# CH32F_V208W-R0.net
KiCad netlist of a schematic drawn in Altium Designer
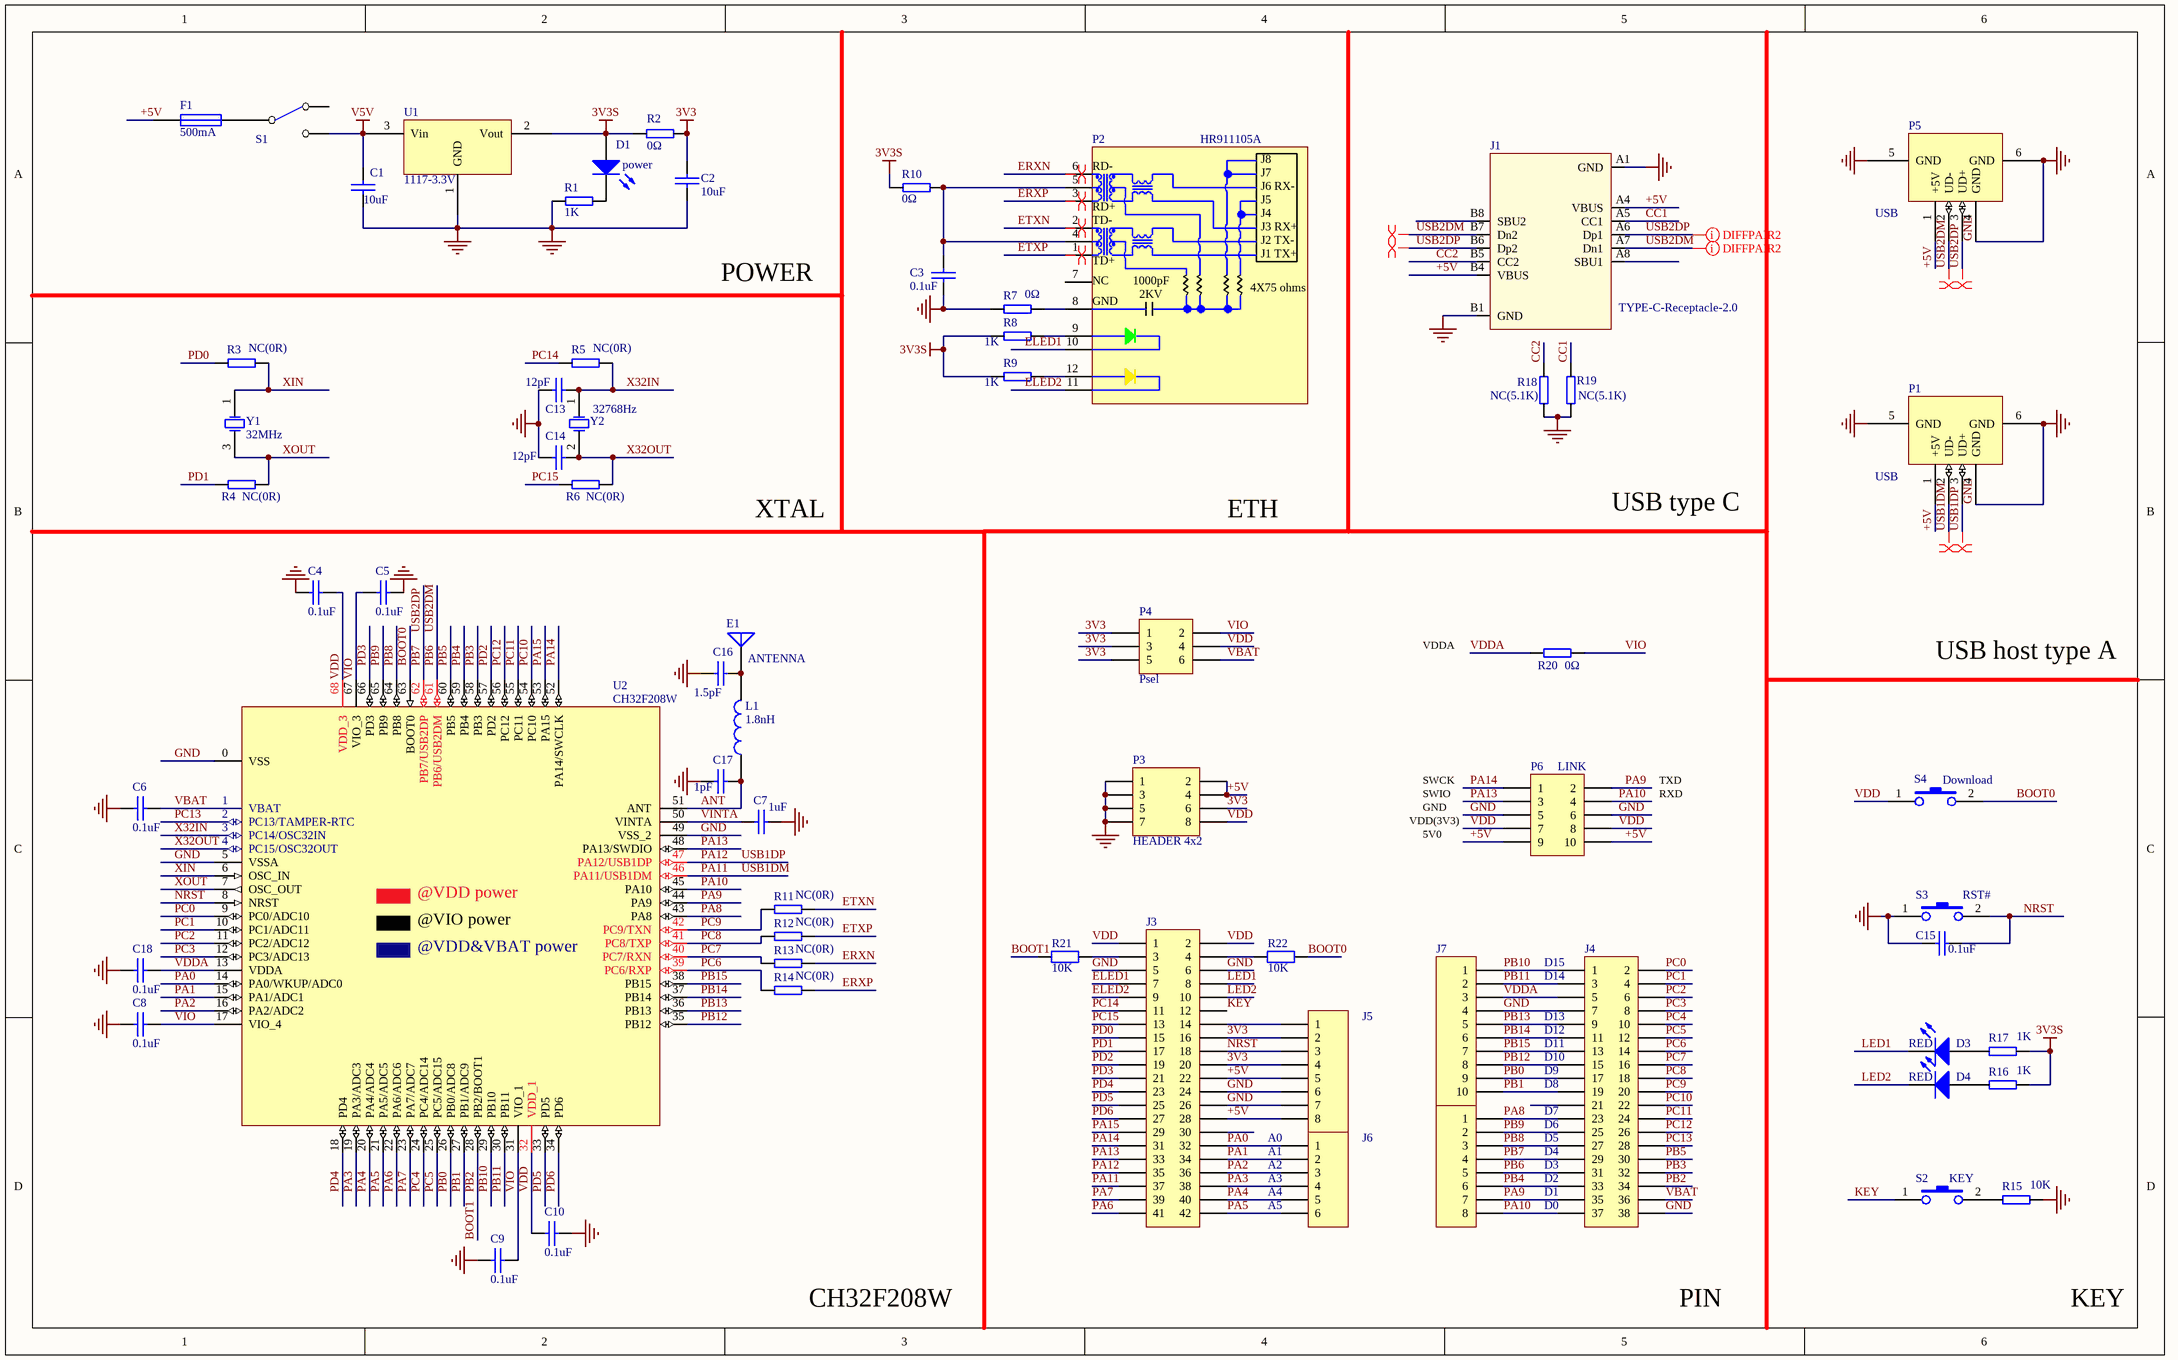
[diagram p0: CH32F&V208W-R0.SchDoc]

(export (version "E")
  (design (tool "Eeschema 10.0.6"))
  (components
    (comp (ref "C1")
      (value "10uF")
      (footprint "3216_C")
      (description "Capacitor")
      (libsource (lib "*") (part "CAP"))
    )
    (comp (ref "C2")
      (value "10uF")
      (footprint "0603_C")
      (description "Capacitor")
      (libsource (lib "*") (part "CAP"))
    )
    (comp (ref "C3")
      (value "0.1uF")
      (footprint "0603_C")
      (description "Capacitor")
      (libsource (lib "*") (part "CAP"))
    )
    (comp (ref "C4")
      (value "0.1uF")
      (footprint "0603_C")
      (description "Capacitor")
      (libsource (lib "") (part "CAP_1"))
    )
    (comp (ref "C5")
      (value "0.1uF")
      (footprint "0603_C")
      (description "Capacitor")
      (libsource (lib "") (part "CAP_1"))
    )
    (comp (ref "C6")
      (value "0.1uF")
      (footprint "0603_C")
      (description "Capacitor")
      (libsource (lib "") (part "CAP_1"))
    )
    (comp (ref "C7")
      (value "1uF")
      (footprint "0603_C")
      (description "Capacitor")
      (libsource (lib "") (part "CAP_1"))
    )
    (comp (ref "C8")
      (value "0.1uF")
      (footprint "0603_C")
      (description "Capacitor")
      (libsource (lib "") (part "CAP_1"))
    )
    (comp (ref "C9")
      (value "0.1uF")
      (footprint "0603_C")
      (description "Capacitor")
      (libsource (lib "") (part "CAP_1"))
    )
    (comp (ref "C10")
      (value "0.1uF")
      (footprint "0603_C")
      (description "Capacitor")
      (libsource (lib "") (part "CAP_1"))
    )
    (comp (ref "C13")
      (value "12pF")
      (footprint "0603_C")
      (description "Capacitor")
      (libsource (lib "*") (part "CAP"))
    )
    (comp (ref "C14")
      (value "12pF")
      (footprint "0603_C")
      (description "Capacitor")
      (libsource (lib "*") (part "CAP"))
    )
    (comp (ref "C15")
      (value "0.1uF")
      (footprint "0603_C")
      (description "Capacitor")
      (libsource (lib "") (part "CAP_1"))
    )
    (comp (ref "C16")
      (value "1.5pF")
      (footprint "0603_C")
      (description "Capacitor")
      (libsource (lib "") (part "CAP_1"))
    )
    (comp (ref "C17")
      (value "1pF")
      (footprint "0603_C")
      (description "Capacitor")
      (libsource (lib "") (part "CAP_1"))
    )
    (comp (ref "C18")
      (value "0.1uF")
      (footprint "0603_C")
      (description "Capacitor")
      (libsource (lib "") (part "CAP_1"))
    )
    (comp (ref "D1")
      (value "power")
      (footprint "0603+")
      (description "Typical INFRARED GaAs LED")
      (fields (field (name "PUBLISHER") "Altium Limited"))
      (libsource (lib "*") (part "LED0"))
    )
    (comp (ref "D3")
      (value "RED")
      (footprint "0603+")
      (description "Typical INFRARED GaAs LED")
      (fields (field (name "PUBLISHER") "Altium Limited"))
      (libsource (lib "*") (part "LED0"))
    )
    (comp (ref "D4")
      (value "RED")
      (footprint "0603+")
      (description "Typical INFRARED GaAs LED")
      (fields (field (name "PUBLISHER") "Altium Limited"))
      (libsource (lib "*") (part "LED0"))
    )
    (comp (ref "E1")
      (value "ANTENNA")
      (footprint "MYPCB:ANT-F-1-2.4G-1.6")
      (description "Generic Antenna")
      (libsource (lib "*") (part "ANTENNA"))
    )
    (comp (ref "F1")
      (value "500mA")
      (footprint "0603")
      (description "Fuse")
      (libsource (lib "wch_sch_others") (part "FUSE1"))
    )
    (comp (ref "J1")
      (value "TYPE-C-Receptacle-2.0")
      (footprint "TYPE-C-Receptacle-2.0")
      (description "Type-C USB2.0 母座")
      (libsource (lib "Miscellaneous SCH Lib") (part "TYPE-C-Receptacle-2.0"))
    )
    (comp (ref "J3")
      (value "Header 21X2")
      (footprint "IDC42-2.54mm")
      (description "Header, 21-Pin, Dual row")
      (fields (field (name "PUBLISHER") "Altium Limited"))
      (libsource (lib "PCB_Project") (part "Header 21X2"))
    )
    (comp (ref "J4")
      (value "Header 19X2")
      (footprint "IDC38-2.54mm")
      (description "Header, 19-Pin, Dual row")
      (fields (field (name "PUBLISHER") "Altium Limited"))
      (libsource (lib "Miscellaneous Connectors") (part "Header 19X2"))
    )
    (comp (ref "J5")
      (value "Header 8")
      (footprint "SIP8-2.54mm")
      (description "Header, 8-Pin")
      (fields (field (name "PUBLISHER") "Altium Limited"))
      (libsource (lib "") (part "Header 8_1"))
    )
    (comp (ref "J6")
      (value "Header 6")
      (footprint "SIP6-2.54MM")
      (description "Header, 6-Pin")
      (fields (field (name "PUBLISHER") "Altium Limited"))
      (libsource (lib "Miscellaneous Connectors") (part "Header 6"))
    )
    (comp (ref "J7")
      (value "Header 10")
      (footprint "SIP10-2.54mm")
      (description "Header, 10-Pin")
      (fields (field (name "PUBLISHER") "Altium Limited"))
      (libsource (lib "Miscellaneous Connectors") (part "Header 10"))
    )
    (comp (ref "J8")
      (value "Header 8")
      (footprint "SIP8-2.54mm")
      (description "Header, 8-Pin")
      (fields (field (name "PUBLISHER") "Altium Limited"))
      (libsource (lib "Miscellaneous Connectors") (part "Header 8"))
    )
    (comp (ref "L1") (value "1.8nH") (footprint "0603") (libsource (lib "*") (part "INDUCTOR")))
    (comp (ref "P1")
      (value "USB")
      (footprint "USBAF")
      (description "USB Port")
      (libsource (lib "*") (part "USB"))
    )
    (comp (ref "P2") (value "HR911105A") (footprint "HR911105A") (libsource (lib "*") (part "HR911105A")))
    (comp (ref "P3")
      (value "HEADER 4x2")
      (footprint "MYPCB:IDC8-2.54mm")
      (description "Header, 4-Pin, Dual row")
      (libsource (lib "wch_sch_others") (part "HEADER 4x2"))
    )
    (comp (ref "P4")
      (value "Psel")
      (footprint "IDC6-2.54mm")
      (description "Header, 3-Pin, Dual row, Right Angle")
      (fields (field (name "PUBLISHER") "Altium Limited"))
      (libsource (lib "Miscellaneous Connectors") (part "Header 3X2H"))
    )
    (comp (ref "P5")
      (value "USB")
      (footprint "USBAF")
      (description "USB Port")
      (libsource (lib "*") (part "USB"))
    )
    (comp (ref "P6")
      (value "LINK")
      (footprint "IDC10-2.54mm")
      (description "Header, 5-Pin, Dual row, Right Angle")
      (fields (field (name "PUBLISHER") "Altium Limited"))
      (libsource (lib "Miscellaneous Connectors") (part "Header 5X2H"))
    )
    (comp (ref "R1") (value "1K") (footprint "0603") (libsource (lib "wch_sch_others") (part "RES")))
    (comp (ref "R2") (value "0Ω") (footprint "0603") (libsource (lib "wch_sch_others") (part "RES")))
    (comp (ref "R3") (value "NC(0R)") (footprint "0603") (libsource (lib "wch_sch_others") (part "RES")))
    (comp (ref "R4") (value "NC(0R)") (footprint "0603") (libsource (lib "wch_sch_others") (part "RES")))
    (comp (ref "R5") (value "NC(0R)") (footprint "0603") (libsource (lib "wch_sch_others") (part "RES")))
    (comp (ref "R6") (value "NC(0R)") (footprint "0603") (libsource (lib "wch_sch_others") (part "RES")))
    (comp (ref "R7") (value "0Ω") (footprint "0603") (libsource (lib "wch_sch_others") (part "RES")))
    (comp (ref "R8") (value "1K") (footprint "0603") (libsource (lib "wch_sch_others") (part "RES")))
    (comp (ref "R9") (value "1K") (footprint "0603") (libsource (lib "wch_sch_others") (part "RES")))
    (comp (ref "R10") (value "0Ω") (footprint "0603") (libsource (lib "wch_sch_others") (part "RES")))
    (comp (ref "R11") (value "NC(0R)") (footprint "0603") (libsource (lib "wch_sch_others") (part "RES")))
    (comp (ref "R12") (value "NC(0R)") (footprint "0603") (libsource (lib "wch_sch_others") (part "RES")))
    (comp (ref "R13") (value "NC(0R)") (footprint "0603") (libsource (lib "wch_sch_others") (part "RES")))
    (comp (ref "R14") (value "NC(0R)") (footprint "0603") (libsource (lib "wch_sch_others") (part "RES")))
    (comp (ref "R15") (value "10K") (footprint "0603") (libsource (lib "wch_sch_others") (part "RES")))
    (comp (ref "R16") (value "1K") (footprint "0603") (libsource (lib "wch_sch_others") (part "RES")))
    (comp (ref "R17") (value "1K") (footprint "0603") (libsource (lib "wch_sch_others") (part "RES")))
    (comp (ref "R18") (value "NC(5.1K)") (footprint "0603") (libsource (lib "wch_sch_others") (part "RES")))
    (comp (ref "R19") (value "NC(5.1K)") (footprint "0603") (libsource (lib "wch_sch_others") (part "RES")))
    (comp (ref "R20") (value "0Ω") (footprint "0603") (libsource (lib "*") (part "R")))
    (comp (ref "R21")
      (value "10K")
      (footprint "0603")
      (description "Resistor")
      (libsource (lib "Miscellaneous Devices") (part "Res2"))
    )
    (comp (ref "R22")
      (value "10K")
      (footprint "0603")
      (description "Resistor")
      (libsource (lib "Miscellaneous Devices") (part "Res2"))
    )
    (comp (ref "S1") (value "SW SPDT") (footprint "KEY_B") (libsource (lib "*") (part "SW SPDT")))
    (comp (ref "S2")
      (value "KEY")
      (footprint "SMD_6.1x3.65x2.5mm-KEY")
      (libsource (lib "wch_sch_others") (part "KEY1"))
    )
    (comp (ref "S3")
      (value "RST#")
      (footprint "SMD_6.1x3.65x2.5mm-KEY")
      (libsource (lib "wch_sch_others") (part "KEY1"))
    )
    (comp (ref "S4")
      (value "Download")
      (footprint "SMD_6.1x3.65x2.5mm-KEY")
      (libsource (lib "wch_sch_others") (part "KEY1"))
    )
    (comp (ref "U1")
      (value "1117-3.3V")
      (footprint "SOT-223")
      (libsource (lib "wch_sch_others") (part "1117-3.3V"))
    )
    (comp (ref "U2")
      (value "CH32F208W")
      (footprint "QFN68_8x8")
      (description "ARM M3 BLE5.3 MCU, 10M Ethernet, 2*USB, CAN")
      (libsource (lib "CHXXX") (part "CH32F208W"))
    )
    (comp (ref "Y1")
      (value "32MHz")
      (footprint "XT3225")
      (description "Crystal Oscillator")
      (fields (field (name "PUBLISHER") "Altium Limited"))
      (libsource (lib "") (part "XTAL_1"))
    )
    (comp (ref "Y2")
      (value "32768Hz")
      (footprint "FC-135")
      (description "Crystal Oscillator")
      (fields (field (name "PUBLISHER") "Altium Limited"))
      (libsource (lib "*") (part "XTAL"))
    )
  )
  (nets
    (net (code "1") (name "/+5V") (class "Default")
      (node (ref "F1") (pin "1") (pinfunction "1_1") (pintype "passive"))
      (node (ref "J1") (pin "A4") (pinfunction "VBUS_A4") (pintype "passive"))
      (node (ref "J1") (pin "B4") (pinfunction "VBUS_B4") (pintype "passive"))
      (node (ref "J3") (pin "22") (pinfunction "22_22") (pintype "passive"))
      (node (ref "J3") (pin "28") (pinfunction "28_28") (pintype "passive"))
      (node (ref "J5") (pin "5") (pinfunction "5_5") (pintype "passive"))
      (node (ref "J5") (pin "8") (pinfunction "8_8") (pintype "passive"))
      (node (ref "P1") (pin "1") (pinfunction "+5V_1") (pintype "power_in"))
      (node (ref "P3") (pin "2") (pinfunction "2_2") (pintype "passive"))
      (node (ref "P3") (pin "4") (pinfunction "4_4") (pintype "passive"))
      (node (ref "P5") (pin "1") (pinfunction "+5V_1") (pintype "power_in"))
      (node (ref "P6") (pin "10") (pinfunction "10_10") (pintype "passive"))
      (node (ref "P6") (pin "9") (pinfunction "9_9") (pintype "passive"))
    )
    (net (code "2") (name "/ANT") (class "Default")
      (node (ref "C17") (pin "2") (pinfunction "2_2") (pintype "passive"))
      (node (ref "L1") (pin "1") (pinfunction "1_1") (pintype "passive"))
      (node (ref "U2") (pin "51") (pinfunction "ANT_51") (pintype "power_in"))
    )
    (net (code "3") (name "/BOOT0") (class "Default")
      (node (ref "R22") (pin "2") (pinfunction "2_2") (pintype "passive"))
      (node (ref "S4") (pin "2") (pinfunction "2_2") (pintype "passive"))
      (node (ref "U2") (pin "63") (pinfunction "BOOT0_63") (pintype "input"))
    )
    (net (code "4") (name "/BOOT1") (class "Default")
      (node (ref "J4") (pin "34") (pinfunction "34_34") (pintype "passive"))
      (node (ref "R21") (pin "1") (pinfunction "1_1") (pintype "passive"))
      (node (ref "U2") (pin "28") (pinfunction "PB2/BOOT1_28") (pintype "bidirectional"))
    )
    (net (code "5") (name "/CC1") (class "Default")
      (node (ref "J1") (pin "A5") (pinfunction "CC1_A5") (pintype "passive"))
      (node (ref "R19") (pin "1") (pintype "passive"))
    )
    (net (code "6") (name "/CC2") (class "Default")
      (node (ref "J1") (pin "B5") (pinfunction "CC2_B5") (pintype "passive"))
      (node (ref "R18") (pin "1") (pintype "passive"))
    )
    (net (code "7") (name "/ELED1") (class "Default")
      (node (ref "J3") (pin "7") (pinfunction "7_7") (pintype "passive"))
      (node (ref "P2") (pin "10") (pintype "passive"))
    )
    (net (code "8") (name "/ELED2") (class "Default")
      (node (ref "J3") (pin "9") (pinfunction "9_9") (pintype "passive"))
      (node (ref "P2") (pin "11") (pintype "passive"))
    )
    (net (code "9") (name "/ERXN") (class "Default")
      (node (ref "P2") (pin "6") (pintype "passive"))
      (node (ref "R13") (pin "2") (pintype "passive"))
    )
    (net (code "10") (name "/ERXP") (class "Default")
      (node (ref "P2") (pin "3") (pintype "passive"))
      (node (ref "R14") (pin "2") (pintype "passive"))
    )
    (net (code "11") (name "/ETXN") (class "Default")
      (node (ref "P2") (pin "2") (pintype "passive"))
      (node (ref "R11") (pin "2") (pintype "passive"))
    )
    (net (code "12") (name "/ETXP") (class "Default")
      (node (ref "P2") (pin "1") (pintype "passive"))
      (node (ref "R12") (pin "2") (pintype "passive"))
    )
    (net (code "13") (name "/KEY") (class "Default")
      (node (ref "J3") (pin "12") (pinfunction "12_12") (pintype "passive"))
      (node (ref "S2") (pin "1") (pinfunction "1_1") (pintype "passive"))
    )
    (net (code "14") (name "/LED1") (class "Default")
      (node (ref "D3") (pin "2") (pinfunction "K_2") (pintype "passive"))
      (node (ref "J3") (pin "8") (pinfunction "8_8") (pintype "passive"))
    )
    (net (code "15") (name "/LED2") (class "Default")
      (node (ref "D4") (pin "2") (pinfunction "K_2") (pintype "passive"))
      (node (ref "J3") (pin "10") (pinfunction "10_10") (pintype "passive"))
    )
    (net (code "16") (name "/NRST") (class "Default")
      (node (ref "C15") (pin "2") (pinfunction "2_2") (pintype "passive"))
      (node (ref "J3") (pin "18") (pinfunction "18_18") (pintype "passive"))
      (node (ref "J5") (pin "3") (pinfunction "3_3") (pintype "passive"))
      (node (ref "S3") (pin "2") (pinfunction "2_2") (pintype "passive"))
      (node (ref "U2") (pin "8") (pinfunction "NRST_8") (pintype "input"))
    )
    (net (code "17") (name "/PA0") (class "Default")
      (node (ref "J3") (pin "32") (pinfunction "32_32") (pintype "passive"))
      (node (ref "J6") (pin "1") (pinfunction "1_1") (pintype "passive"))
      (node (ref "U2") (pin "14") (pinfunction "PA0/WKUP/ADC0_14") (pintype "bidirectional"))
    )
    (net (code "18") (name "/PA1") (class "Default")
      (node (ref "J3") (pin "34") (pinfunction "34_34") (pintype "passive"))
      (node (ref "J6") (pin "2") (pinfunction "2_2") (pintype "passive"))
      (node (ref "U2") (pin "15") (pinfunction "PA1/ADC1_15") (pintype "bidirectional"))
    )
    (net (code "19") (name "/PA2") (class "Default")
      (node (ref "J3") (pin "36") (pinfunction "36_36") (pintype "passive"))
      (node (ref "J6") (pin "3") (pinfunction "3_3") (pintype "passive"))
      (node (ref "U2") (pin "16") (pinfunction "PA2/ADC2_16") (pintype "bidirectional"))
    )
    (net (code "20") (name "/PA3") (class "Default")
      (node (ref "J3") (pin "38") (pinfunction "38_38") (pintype "passive"))
      (node (ref "J6") (pin "4") (pinfunction "4_4") (pintype "passive"))
      (node (ref "U2") (pin "19") (pinfunction "PA3/ADC3_19") (pintype "bidirectional"))
    )
    (net (code "21") (name "/PA4") (class "Default")
      (node (ref "J3") (pin "40") (pinfunction "40_40") (pintype "passive"))
      (node (ref "J6") (pin "5") (pinfunction "5_5") (pintype "passive"))
      (node (ref "U2") (pin "20") (pinfunction "PA4/ADC4_20") (pintype "bidirectional"))
    )
    (net (code "22") (name "/PA5") (class "Default")
      (node (ref "J3") (pin "42") (pinfunction "42_42") (pintype "passive"))
      (node (ref "J6") (pin "6") (pinfunction "6_6") (pintype "passive"))
      (node (ref "U2") (pin "21") (pinfunction "PA5/ADC5_21") (pintype "bidirectional"))
    )
    (net (code "23") (name "/PA6") (class "Default")
      (node (ref "J3") (pin "41") (pinfunction "41_41") (pintype "passive"))
      (node (ref "U2") (pin "22") (pinfunction "PA6/ADC6_22") (pintype "bidirectional"))
    )
    (net (code "24") (name "/PA7") (class "Default")
      (node (ref "J3") (pin "39") (pinfunction "39_39") (pintype "passive"))
      (node (ref "U2") (pin "23") (pinfunction "PA7/ADC7_23") (pintype "bidirectional"))
    )
    (net (code "25") (name "/PA8") (class "Default")
      (node (ref "J4") (pin "23") (pinfunction "23_23") (pintype "passive"))
      (node (ref "J8") (pin "1") (pinfunction "1_1") (pintype "passive"))
      (node (ref "U2") (pin "43") (pinfunction "PA8_43") (pintype "bidirectional"))
    )
    (net (code "26") (name "/PA9") (class "Default")
      (node (ref "J4") (pin "35") (pinfunction "35_35") (pintype "passive"))
      (node (ref "J8") (pin "7") (pinfunction "7_7") (pintype "passive"))
      (node (ref "P6") (pin "2") (pinfunction "2_2") (pintype "passive"))
      (node (ref "U2") (pin "44") (pinfunction "PA9_44") (pintype "bidirectional"))
    )
    (net (code "27") (name "/PA10") (class "Default")
      (node (ref "J4") (pin "37") (pinfunction "37_37") (pintype "passive"))
      (node (ref "J8") (pin "8") (pinfunction "8_8") (pintype "passive"))
      (node (ref "P6") (pin "4") (pinfunction "4_4") (pintype "passive"))
      (node (ref "U2") (pin "45") (pinfunction "PA10_45") (pintype "bidirectional"))
    )
    (net (code "28") (name "/PA11") (class "Default")
      (node (ref "J3") (pin "37") (pinfunction "37_37") (pintype "passive"))
      (node (ref "P1") (pin "2") (pinfunction "UD-_2") (pintype "bidirectional"))
      (node (ref "U2") (pin "46") (pinfunction "PA11/USB1DM_46") (pintype "bidirectional"))
    )
    (net (code "29") (name "/PA12") (class "Default")
      (node (ref "J3") (pin "35") (pinfunction "35_35") (pintype "passive"))
      (node (ref "P1") (pin "3") (pinfunction "UD+_3") (pintype "bidirectional"))
      (node (ref "U2") (pin "47") (pinfunction "PA12/USB1DP_47") (pintype "bidirectional"))
    )
    (net (code "30") (name "/PA13") (class "Default")
      (node (ref "J3") (pin "33") (pinfunction "33_33") (pintype "passive"))
      (node (ref "P6") (pin "3") (pinfunction "3_3") (pintype "passive"))
      (node (ref "U2") (pin "48") (pinfunction "PA13/SWDIO_48") (pintype "bidirectional"))
    )
    (net (code "31") (name "/PA14") (class "Default")
      (node (ref "J3") (pin "31") (pinfunction "31_31") (pintype "passive"))
      (node (ref "P6") (pin "1") (pinfunction "1_1") (pintype "passive"))
      (node (ref "U2") (pin "52") (pinfunction "PA14/SWCLK_52") (pintype "bidirectional"))
    )
    (net (code "32") (name "/PA15") (class "Default")
      (node (ref "J3") (pin "29") (pinfunction "29_29") (pintype "passive"))
      (node (ref "U2") (pin "53") (pinfunction "PA15_53") (pintype "bidirectional"))
    )
    (net (code "33") (name "/PB0") (class "Default")
      (node (ref "J4") (pin "17") (pinfunction "17_17") (pintype "passive"))
      (node (ref "J7") (pin "9") (pinfunction "9_9") (pintype "passive"))
      (node (ref "U2") (pin "26") (pinfunction "PB0/ADC8_26") (pintype "bidirectional"))
    )
    (net (code "34") (name "/PB1") (class "Default")
      (node (ref "J4") (pin "19") (pinfunction "19_19") (pintype "passive"))
      (node (ref "J7") (pin "10") (pinfunction "10_10") (pintype "passive"))
      (node (ref "U2") (pin "27") (pinfunction "PB1/ADC9_27") (pintype "bidirectional"))
    )
    (net (code "35") (name "/PB3") (class "Default")
      (node (ref "J4") (pin "32") (pinfunction "32_32") (pintype "passive"))
      (node (ref "U2") (pin "58") (pinfunction "PB3_58") (pintype "bidirectional"))
    )
    (net (code "36") (name "/PB4") (class "Default")
      (node (ref "J4") (pin "33") (pinfunction "33_33") (pintype "passive"))
      (node (ref "J8") (pin "6") (pinfunction "6_6") (pintype "passive"))
      (node (ref "U2") (pin "59") (pinfunction "PB4_59") (pintype "bidirectional"))
    )
    (net (code "37") (name "/PB5") (class "Default")
      (node (ref "J4") (pin "30") (pinfunction "30_30") (pintype "passive"))
      (node (ref "U2") (pin "60") (pinfunction "PB5_60") (pintype "bidirectional"))
    )
    (net (code "38") (name "/PB6") (class "Default")
      (node (ref "J1") (pin "A7") (pinfunction "Dn1_A7") (pintype "passive"))
      (node (ref "J1") (pin "B7") (pinfunction "Dn2_B7") (pintype "passive"))
      (node (ref "J4") (pin "31") (pinfunction "31_31") (pintype "passive"))
      (node (ref "J8") (pin "5") (pinfunction "5_5") (pintype "passive"))
      (node (ref "P5") (pin "2") (pinfunction "UD-_2") (pintype "bidirectional"))
      (node (ref "U2") (pin "61") (pinfunction "PB6/USB2DM_61") (pintype "bidirectional"))
    )
    (net (code "39") (name "/PB7") (class "Default")
      (node (ref "J1") (pin "A6") (pinfunction "Dp1_A6") (pintype "passive"))
      (node (ref "J1") (pin "B6") (pinfunction "Dp2_B6") (pintype "passive"))
      (node (ref "J4") (pin "29") (pinfunction "29_29") (pintype "passive"))
      (node (ref "J8") (pin "4") (pinfunction "4_4") (pintype "passive"))
      (node (ref "P5") (pin "3") (pinfunction "UD+_3") (pintype "bidirectional"))
      (node (ref "U2") (pin "62") (pinfunction "PB7/USB2DP_62") (pintype "bidirectional"))
    )
    (net (code "40") (name "/PB8") (class "Default")
      (node (ref "J4") (pin "27") (pinfunction "27_27") (pintype "passive"))
      (node (ref "J8") (pin "3") (pinfunction "3_3") (pintype "passive"))
      (node (ref "U2") (pin "64") (pinfunction "PB8_64") (pintype "bidirectional"))
    )
    (net (code "41") (name "/PB9") (class "Default")
      (node (ref "J4") (pin "25") (pinfunction "25_25") (pintype "passive"))
      (node (ref "J8") (pin "2") (pinfunction "2_2") (pintype "passive"))
      (node (ref "U2") (pin "65") (pinfunction "PB9_65") (pintype "bidirectional"))
    )
    (net (code "42") (name "/PB10") (class "Default")
      (node (ref "J4") (pin "1") (pinfunction "1_1") (pintype "passive"))
      (node (ref "J7") (pin "1") (pinfunction "1_1") (pintype "passive"))
      (node (ref "U2") (pin "29") (pinfunction "PB10_29") (pintype "bidirectional"))
    )
    (net (code "43") (name "/PB11") (class "Default")
      (node (ref "J4") (pin "3") (pinfunction "3_3") (pintype "passive"))
      (node (ref "J7") (pin "2") (pinfunction "2_2") (pintype "passive"))
      (node (ref "U2") (pin "30") (pinfunction "PB11_30") (pintype "bidirectional"))
    )
    (net (code "44") (name "/PB12") (class "Default")
      (node (ref "J4") (pin "15") (pinfunction "15_15") (pintype "passive"))
      (node (ref "J7") (pin "8") (pinfunction "8_8") (pintype "passive"))
      (node (ref "U2") (pin "35") (pinfunction "PB12_35") (pintype "bidirectional"))
    )
    (net (code "45") (name "/PB13") (class "Default")
      (node (ref "J4") (pin "9") (pinfunction "9_9") (pintype "passive"))
      (node (ref "J7") (pin "5") (pinfunction "5_5") (pintype "passive"))
      (node (ref "U2") (pin "36") (pinfunction "PB13_36") (pintype "bidirectional"))
    )
    (net (code "46") (name "/PB14") (class "Default")
      (node (ref "J4") (pin "11") (pinfunction "11_11") (pintype "passive"))
      (node (ref "J7") (pin "6") (pinfunction "6_6") (pintype "passive"))
      (node (ref "U2") (pin "37") (pinfunction "PB14_37") (pintype "bidirectional"))
    )
    (net (code "47") (name "/PB15") (class "Default")
      (node (ref "J4") (pin "13") (pinfunction "13_13") (pintype "passive"))
      (node (ref "J7") (pin "7") (pinfunction "7_7") (pintype "passive"))
      (node (ref "U2") (pin "38") (pinfunction "PB15_38") (pintype "bidirectional"))
    )
    (net (code "48") (name "/PC0") (class "Default")
      (node (ref "J4") (pin "2") (pinfunction "2_2") (pintype "passive"))
      (node (ref "U2") (pin "9") (pinfunction "PC0/ADC10_9") (pintype "bidirectional"))
    )
    (net (code "49") (name "/PC1") (class "Default")
      (node (ref "J4") (pin "4") (pinfunction "4_4") (pintype "passive"))
      (node (ref "U2") (pin "10") (pinfunction "PC1/ADC11_10") (pintype "bidirectional"))
    )
    (net (code "50") (name "/PC2") (class "Default")
      (node (ref "J4") (pin "6") (pinfunction "6_6") (pintype "passive"))
      (node (ref "U2") (pin "11") (pinfunction "PC2/ADC12_11") (pintype "bidirectional"))
    )
    (net (code "51") (name "/PC3") (class "Default")
      (node (ref "J4") (pin "8") (pinfunction "8_8") (pintype "passive"))
      (node (ref "U2") (pin "12") (pinfunction "PC3/ADC13_12") (pintype "bidirectional"))
    )
    (net (code "52") (name "/PC4") (class "Default")
      (node (ref "J4") (pin "10") (pinfunction "10_10") (pintype "passive"))
      (node (ref "U2") (pin "24") (pinfunction "PC4/ADC14_24") (pintype "bidirectional"))
    )
    (net (code "53") (name "/PC5") (class "Default")
      (node (ref "J4") (pin "12") (pinfunction "12_12") (pintype "passive"))
      (node (ref "U2") (pin "25") (pinfunction "PC5/ADC15_25") (pintype "bidirectional"))
    )
    (net (code "54") (name "/PC6") (class "Default")
      (node (ref "J4") (pin "14") (pinfunction "14_14") (pintype "passive"))
      (node (ref "R14") (pin "1") (pintype "passive"))
      (node (ref "U2") (pin "39") (pinfunction "PC6/RXP_39") (pintype "bidirectional"))
    )
    (net (code "55") (name "/PC7") (class "Default")
      (node (ref "J4") (pin "16") (pinfunction "16_16") (pintype "passive"))
      (node (ref "R13") (pin "1") (pintype "passive"))
      (node (ref "U2") (pin "40") (pinfunction "PC7/RXN_40") (pintype "bidirectional"))
    )
    (net (code "56") (name "/PC8") (class "Default")
      (node (ref "J4") (pin "18") (pinfunction "18_18") (pintype "passive"))
      (node (ref "R12") (pin "1") (pintype "passive"))
      (node (ref "U2") (pin "41") (pinfunction "PC8/TXP_41") (pintype "bidirectional"))
    )
    (net (code "57") (name "/PC9") (class "Default")
      (node (ref "J4") (pin "20") (pinfunction "20_20") (pintype "passive"))
      (node (ref "R11") (pin "1") (pintype "passive"))
      (node (ref "U2") (pin "42") (pinfunction "PC9/TXN_42") (pintype "bidirectional"))
    )
    (net (code "58") (name "/PC10") (class "Default")
      (node (ref "J4") (pin "22") (pinfunction "22_22") (pintype "passive"))
      (node (ref "U2") (pin "54") (pinfunction "PC10_54") (pintype "bidirectional"))
    )
    (net (code "59") (name "/PC11") (class "Default")
      (node (ref "J4") (pin "24") (pinfunction "24_24") (pintype "passive"))
      (node (ref "U2") (pin "55") (pinfunction "PC11_55") (pintype "bidirectional"))
    )
    (net (code "60") (name "/PC12") (class "Default")
      (node (ref "J4") (pin "26") (pinfunction "26_26") (pintype "passive"))
      (node (ref "U2") (pin "56") (pinfunction "PC12_56") (pintype "bidirectional"))
    )
    (net (code "61") (name "/PC13") (class "Default")
      (node (ref "J4") (pin "28") (pinfunction "28_28") (pintype "passive"))
      (node (ref "U2") (pin "2") (pinfunction "PC13/TAMPER-RTC_2") (pintype "bidirectional"))
    )
    (net (code "62") (name "/PC14") (class "Default")
      (node (ref "J3") (pin "11") (pinfunction "11_11") (pintype "passive"))
      (node (ref "R5") (pin "1") (pintype "passive"))
    )
    (net (code "63") (name "/PC15") (class "Default")
      (node (ref "J3") (pin "13") (pinfunction "13_13") (pintype "passive"))
      (node (ref "R6") (pin "1") (pintype "passive"))
    )
    (net (code "64") (name "/PD0") (class "Default")
      (node (ref "J3") (pin "15") (pinfunction "15_15") (pintype "passive"))
      (node (ref "R3") (pin "1") (pintype "passive"))
    )
    (net (code "65") (name "/PD1") (class "Default")
      (node (ref "J3") (pin "17") (pinfunction "17_17") (pintype "passive"))
      (node (ref "R4") (pin "1") (pintype "passive"))
    )
    (net (code "66") (name "/PD2") (class "Default")
      (node (ref "J3") (pin "19") (pinfunction "19_19") (pintype "passive"))
      (node (ref "U2") (pin "57") (pinfunction "PD2_57") (pintype "bidirectional"))
    )
    (net (code "67") (name "/PD3") (class "Default")
      (node (ref "J3") (pin "21") (pinfunction "21_21") (pintype "passive"))
      (node (ref "U2") (pin "66") (pinfunction "PD3_66") (pintype "bidirectional"))
    )
    (net (code "68") (name "/PD4") (class "Default")
      (node (ref "J3") (pin "23") (pinfunction "23_23") (pintype "passive"))
      (node (ref "U2") (pin "18") (pinfunction "PD4_18") (pintype "bidirectional"))
    )
    (net (code "69") (name "/PD5") (class "Default")
      (node (ref "J3") (pin "25") (pinfunction "25_25") (pintype "passive"))
      (node (ref "U2") (pin "33") (pinfunction "PD5_33") (pintype "bidirectional"))
    )
    (net (code "70") (name "/PD6") (class "Default")
      (node (ref "J3") (pin "27") (pinfunction "27_27") (pintype "passive"))
      (node (ref "U2") (pin "34") (pinfunction "PD6_34") (pintype "bidirectional"))
    )
    (net (code "71") (name "/VBAT") (class "Default")
      (node (ref "C6") (pin "1") (pinfunction "1_1") (pintype "passive"))
      (node (ref "J4") (pin "36") (pinfunction "36_36") (pintype "passive"))
      (node (ref "P4") (pin "6") (pinfunction "6_6") (pintype "passive"))
      (node (ref "U2") (pin "1") (pinfunction "VBAT_1") (pintype "power_in"))
    )
    (net (code "72") (name "/VDD") (class "Default")
      (node (ref "C10") (pin "2") (pinfunction "2_2") (pintype "passive"))
      (node (ref "C4") (pin "1") (pinfunction "1_1") (pintype "passive"))
      (node (ref "J3") (pin "1") (pinfunction "1_1") (pintype "passive"))
      (node (ref "J3") (pin "2") (pinfunction "2_2") (pintype "passive"))
      (node (ref "P3") (pin "8") (pinfunction "8_8") (pintype "passive"))
      (node (ref "P4") (pin "4") (pinfunction "4_4") (pintype "passive"))
      (node (ref "P6") (pin "7") (pinfunction "7_7") (pintype "passive"))
      (node (ref "P6") (pin "8") (pinfunction "8_8") (pintype "passive"))
      (node (ref "S4") (pin "1") (pinfunction "1_1") (pintype "passive"))
      (node (ref "U2") (pin "32") (pinfunction "VDD_1_32") (pintype "power_in"))
      (node (ref "U2") (pin "68") (pinfunction "VDD_3_68") (pintype "power_in"))
    )
    (net (code "73") (name "/VDDA") (class "Default")
      (node (ref "C18") (pin "1") (pinfunction "1_1") (pintype "passive"))
      (node (ref "J4") (pin "5") (pinfunction "5_5") (pintype "passive"))
      (node (ref "J7") (pin "3") (pinfunction "3_3") (pintype "passive"))
      (node (ref "R20") (pin "2") (pinfunction "2_2") (pintype "passive"))
      (node (ref "U2") (pin "13") (pinfunction "VDDA_13") (pintype "power_in"))
    )
    (net (code "74") (name "/VINTA") (class "Default")
      (node (ref "C7") (pin "1") (pinfunction "1_1") (pintype "passive"))
      (node (ref "U2") (pin "50") (pinfunction "VINTA_50") (pintype "power_in"))
    )
    (net (code "75") (name "/VIO") (class "Default")
      (node (ref "C5") (pin "2") (pinfunction "2_2") (pintype "passive"))
      (node (ref "C8") (pin "1") (pinfunction "1_1") (pintype "passive"))
      (node (ref "C9") (pin "1") (pinfunction "1_1") (pintype "passive"))
      (node (ref "P4") (pin "2") (pinfunction "2_2") (pintype "passive"))
      (node (ref "R20") (pin "1") (pinfunction "1_1") (pintype "passive"))
      (node (ref "U2") (pin "17") (pinfunction "VIO_4_17") (pintype "power_in"))
      (node (ref "U2") (pin "31") (pinfunction "VIO_1_31") (pintype "power_in"))
      (node (ref "U2") (pin "67") (pinfunction "VIO_3_67") (pintype "power_in"))
    )
    (net (code "76") (name "/X32IN") (class "Default")
      (node (ref "C13") (pin "2") (pinfunction "2_2") (pintype "passive"))
      (node (ref "R5") (pin "2") (pintype "passive"))
      (node (ref "U2") (pin "3") (pinfunction "PC14/OSC32IN_3") (pintype "bidirectional"))
      (node (ref "Y2") (pin "1") (pinfunction "OSC1_1") (pintype "passive"))
    )
    (net (code "77") (name "/X32OUT") (class "Default")
      (node (ref "C14") (pin "2") (pinfunction "2_2") (pintype "passive"))
      (node (ref "R6") (pin "2") (pintype "passive"))
      (node (ref "U2") (pin "4") (pinfunction "PC15/OSC32OUT_4") (pintype "bidirectional"))
      (node (ref "Y2") (pin "2") (pinfunction "OSC2_2") (pintype "passive"))
    )
    (net (code "78") (name "/XIN") (class "Default")
      (node (ref "R3") (pin "2") (pintype "passive"))
      (node (ref "U2") (pin "6") (pinfunction "OSC_IN_6") (pintype "input"))
      (node (ref "Y1") (pin "1") (pinfunction "OSC1_1") (pintype "passive"))
    )
    (net (code "79") (name "/XOUT") (class "Default")
      (node (ref "R4") (pin "2") (pintype "passive"))
      (node (ref "U2") (pin "7") (pinfunction "OSC_OUT_7") (pintype "output"))
      (node (ref "Y1") (pin "3") (pinfunction "OSC2_3") (pintype "passive"))
    )
    (net (code "80") (name "3V3") (class "Default")
      (node (ref "C2") (pin "1") (pinfunction "1_1") (pintype "passive"))
      (node (ref "J3") (pin "16") (pinfunction "16_16") (pintype "passive"))
      (node (ref "J3") (pin "20") (pinfunction "20_20") (pintype "passive"))
      (node (ref "J5") (pin "2") (pinfunction "2_2") (pintype "passive"))
      (node (ref "J5") (pin "4") (pinfunction "4_4") (pintype "passive"))
      (node (ref "P3") (pin "6") (pinfunction "6_6") (pintype "passive"))
      (node (ref "P4") (pin "1") (pinfunction "1_1") (pintype "passive"))
      (node (ref "P4") (pin "3") (pinfunction "3_3") (pintype "passive"))
      (node (ref "P4") (pin "5") (pinfunction "5_5") (pintype "passive"))
      (node (ref "R2") (pin "1") (pintype "passive"))
    )
    (net (code "81") (name "3V3S") (class "Default")
      (node (ref "D1") (pin "1") (pinfunction "A_1") (pintype "passive"))
      (node (ref "R10") (pin "2") (pintype "passive"))
      (node (ref "R16") (pin "1") (pintype "passive"))
      (node (ref "R17") (pin "1") (pintype "passive"))
      (node (ref "R2") (pin "2") (pintype "passive"))
      (node (ref "R8") (pin "1") (pintype "passive"))
      (node (ref "R9") (pin "1") (pintype "passive"))
      (node (ref "U1") (pin "2") (pinfunction "Vout_2") (pintype "passive"))
    )
    (net (code "82") (name "GND") (class "Default")
      (node (ref "C1") (pin "2") (pinfunction "2_2") (pintype "passive"))
      (node (ref "C10") (pin "1") (pinfunction "1_1") (pintype "passive"))
      (node (ref "C13") (pin "1") (pinfunction "1_1") (pintype "passive"))
      (node (ref "C14") (pin "1") (pinfunction "1_1") (pintype "passive"))
      (node (ref "C15") (pin "1") (pinfunction "1_1") (pintype "passive"))
      (node (ref "C16") (pin "1") (pinfunction "1_1") (pintype "passive"))
      (node (ref "C17") (pin "1") (pinfunction "1_1") (pintype "passive"))
      (node (ref "C18") (pin "2") (pinfunction "2_2") (pintype "passive"))
      (node (ref "C2") (pin "2") (pinfunction "2_2") (pintype "passive"))
      (node (ref "C3") (pin "1") (pinfunction "1_1") (pintype "passive"))
      (node (ref "C4") (pin "2") (pinfunction "2_2") (pintype "passive"))
      (node (ref "C5") (pin "1") (pinfunction "1_1") (pintype "passive"))
      (node (ref "C6") (pin "2") (pinfunction "2_2") (pintype "passive"))
      (node (ref "C7") (pin "2") (pinfunction "2_2") (pintype "passive"))
      (node (ref "C8") (pin "2") (pinfunction "2_2") (pintype "passive"))
      (node (ref "C9") (pin "2") (pinfunction "2_2") (pintype "passive"))
      (node (ref "J1") (pin "A1") (pinfunction "GND_A1") (pintype "passive"))
      (node (ref "J1") (pin "B1") (pinfunction "GND_B1") (pintype "passive"))
      (node (ref "J3") (pin "24") (pinfunction "24_24") (pintype "passive"))
      (node (ref "J3") (pin "26") (pinfunction "26_26") (pintype "passive"))
      (node (ref "J3") (pin "5") (pinfunction "5_5") (pintype "passive"))
      (node (ref "J3") (pin "6") (pinfunction "6_6") (pintype "passive"))
      (node (ref "J4") (pin "38") (pinfunction "38_38") (pintype "passive"))
      (node (ref "J4") (pin "7") (pinfunction "7_7") (pintype "passive"))
      (node (ref "J5") (pin "6") (pinfunction "6_6") (pintype "passive"))
      (node (ref "J5") (pin "7") (pinfunction "7_7") (pintype "passive"))
      (node (ref "J7") (pin "4") (pinfunction "4_4") (pintype "passive"))
      (node (ref "P1") (pin "4") (pinfunction "GND_4") (pintype "power_in"))
      (node (ref "P1") (pin "5") (pinfunction "GND_5") (pintype "power_in"))
      (node (ref "P1") (pin "6") (pinfunction "GND_6") (pintype "power_in"))
      (node (ref "P3") (pin "1") (pinfunction "1_1") (pintype "passive"))
      (node (ref "P3") (pin "3") (pinfunction "3_3") (pintype "passive"))
      (node (ref "P3") (pin "5") (pinfunction "5_5") (pintype "passive"))
      (node (ref "P3") (pin "7") (pinfunction "7_7") (pintype "passive"))
      (node (ref "P5") (pin "4") (pinfunction "GND_4") (pintype "power_in"))
      (node (ref "P5") (pin "5") (pinfunction "GND_5") (pintype "power_in"))
      (node (ref "P5") (pin "6") (pinfunction "GND_6") (pintype "power_in"))
      (node (ref "P6") (pin "5") (pinfunction "5_5") (pintype "passive"))
      (node (ref "P6") (pin "6") (pinfunction "6_6") (pintype "passive"))
      (node (ref "R1") (pin "1") (pintype "passive"))
      (node (ref "R15") (pin "1") (pintype "passive"))
      (node (ref "R18") (pin "2") (pintype "passive"))
      (node (ref "R19") (pin "2") (pintype "passive"))
      (node (ref "R7") (pin "1") (pintype "passive"))
      (node (ref "S3") (pin "1") (pinfunction "1_1") (pintype "passive"))
      (node (ref "U1") (pin "1") (pinfunction "GND_1") (pintype "passive"))
      (node (ref "U2") (pin "0") (pinfunction "VSS_0") (pintype "power_in"))
      (node (ref "U2") (pin "49") (pinfunction "VSS_2_49") (pintype "power_in"))
      (node (ref "U2") (pin "5") (pinfunction "VSSA_5") (pintype "power_in"))
    )
    (net (code "83") (name "Net-(C3-Pad2)") (class "Default")
      (node (ref "C3") (pin "2") (pinfunction "2_2") (pintype "passive"))
      (node (ref "P2") (pin "4") (pintype "passive"))
      (node (ref "P2") (pin "5") (pintype "passive"))
      (node (ref "R10") (pin "1") (pintype "passive"))
    )
    (net (code "84") (name "Net-(D1-K)") (class "Default")
      (node (ref "D1") (pin "2") (pinfunction "K_2") (pintype "passive"))
      (node (ref "R1") (pin "2") (pintype "passive"))
    )
    (net (code "85") (name "Net-(D3-A)") (class "Default")
      (node (ref "D3") (pin "1") (pinfunction "A_1") (pintype "passive"))
      (node (ref "R17") (pin "2") (pintype "passive"))
    )
    (net (code "86") (name "Net-(D4-A)") (class "Default")
      (node (ref "D4") (pin "1") (pinfunction "A_1") (pintype "passive"))
      (node (ref "R16") (pin "2") (pintype "passive"))
    )
    (net (code "87") (name "Net-(E1-A)") (class "Default")
      (node (ref "C16") (pin "2") (pinfunction "2_2") (pintype "passive"))
      (node (ref "E1") (pin "1") (pinfunction "A_1") (pintype "passive"))
      (node (ref "L1") (pin "2") (pinfunction "2_2") (pintype "passive"))
    )
    (net (code "88") (name "Net-(J3-Pad3)") (class "Default")
      (node (ref "J3") (pin "3") (pinfunction "3_3") (pintype "passive"))
      (node (ref "R21") (pin "2") (pinfunction "2_2") (pintype "passive"))
    )
    (net (code "89") (name "Net-(J3-Pad4)") (class "Default")
      (node (ref "J3") (pin "4") (pinfunction "4_4") (pintype "passive"))
      (node (ref "R22") (pin "1") (pinfunction "1_1") (pintype "passive"))
    )
    (net (code "90") (name "Net-(J3-Pad14)") (class "Default")
      (node (ref "J3") (pin "14") (pinfunction "14_14") (pintype "passive"))
      (node (ref "J5") (pin "1") (pinfunction "1_1") (pintype "passive"))
    )
    (net (code "91") (name "Net-(P2-Pad8)") (class "Default")
      (node (ref "P2") (pin "8") (pintype "passive"))
      (node (ref "R7") (pin "2") (pintype "passive"))
    )
    (net (code "92") (name "Net-(P2-Pad9)") (class "Default")
      (node (ref "P2") (pin "9") (pintype "passive"))
      (node (ref "R8") (pin "2") (pintype "passive"))
    )
    (net (code "93") (name "Net-(P2-Pad12)") (class "Default")
      (node (ref "P2") (pin "12") (pintype "passive"))
      (node (ref "R9") (pin "2") (pintype "passive"))
    )
    (net (code "94") (name "Net-(R15-Pad2)") (class "Default")
      (node (ref "R15") (pin "2") (pintype "passive"))
      (node (ref "S2") (pin "2") (pinfunction "2_2") (pintype "passive"))
    )
    (net (code "95") (name "Net-(S1-COMMON)") (class "Default")
      (node (ref "F1") (pin "2") (pinfunction "2_2") (pintype "passive"))
      (node (ref "S1") (pin "1") (pinfunction "COMMON_1") (pintype "passive"))
    )
    (net (code "96") (name "V5V") (class "Default")
      (node (ref "C1") (pin "1") (pinfunction "1_1") (pintype "passive"))
      (node (ref "S1") (pin "2") (pinfunction "NC_2") (pintype "passive"))
      (node (ref "U1") (pin "3") (pinfunction "Vin_3") (pintype "passive"))
    )
    (net (code "97") (name "unconnected-(J1-SBU1-PadA8)") (class "Default")
      (node (ref "J1") (pin "A8") (pinfunction "SBU1_A8") (pintype "passive"))
    )
    (net (code "98") (name "unconnected-(J1-SBU2-PadB8)") (class "Default")
      (node (ref "J1") (pin "B8") (pinfunction "SBU2_B8") (pintype "passive"))
    )
    (net (code "99") (name "unconnected-(J3-Pad30)") (class "Default")
      (node (ref "J3") (pin "30") (pinfunction "30_30") (pintype "passive"))
    )
    (net (code "100") (name "unconnected-(J4-Pad21)") (class "Default")
      (node (ref "J4") (pin "21") (pinfunction "21_21") (pintype "passive"))
    )
    (net (code "101") (name "unconnected-(P2-Pad7)") (class "Default")
      (node (ref "P2") (pin "7") (pintype "passive"))
    )
    (net (code "102") (name "unconnected-(S1-NO-Pad3)") (class "Default")
      (node (ref "S1") (pin "3") (pinfunction "NO_3") (pintype "passive"))
    )
  )
)
